# LM3478.net
KiCad netlist of a schematic drawn in Altium Designer
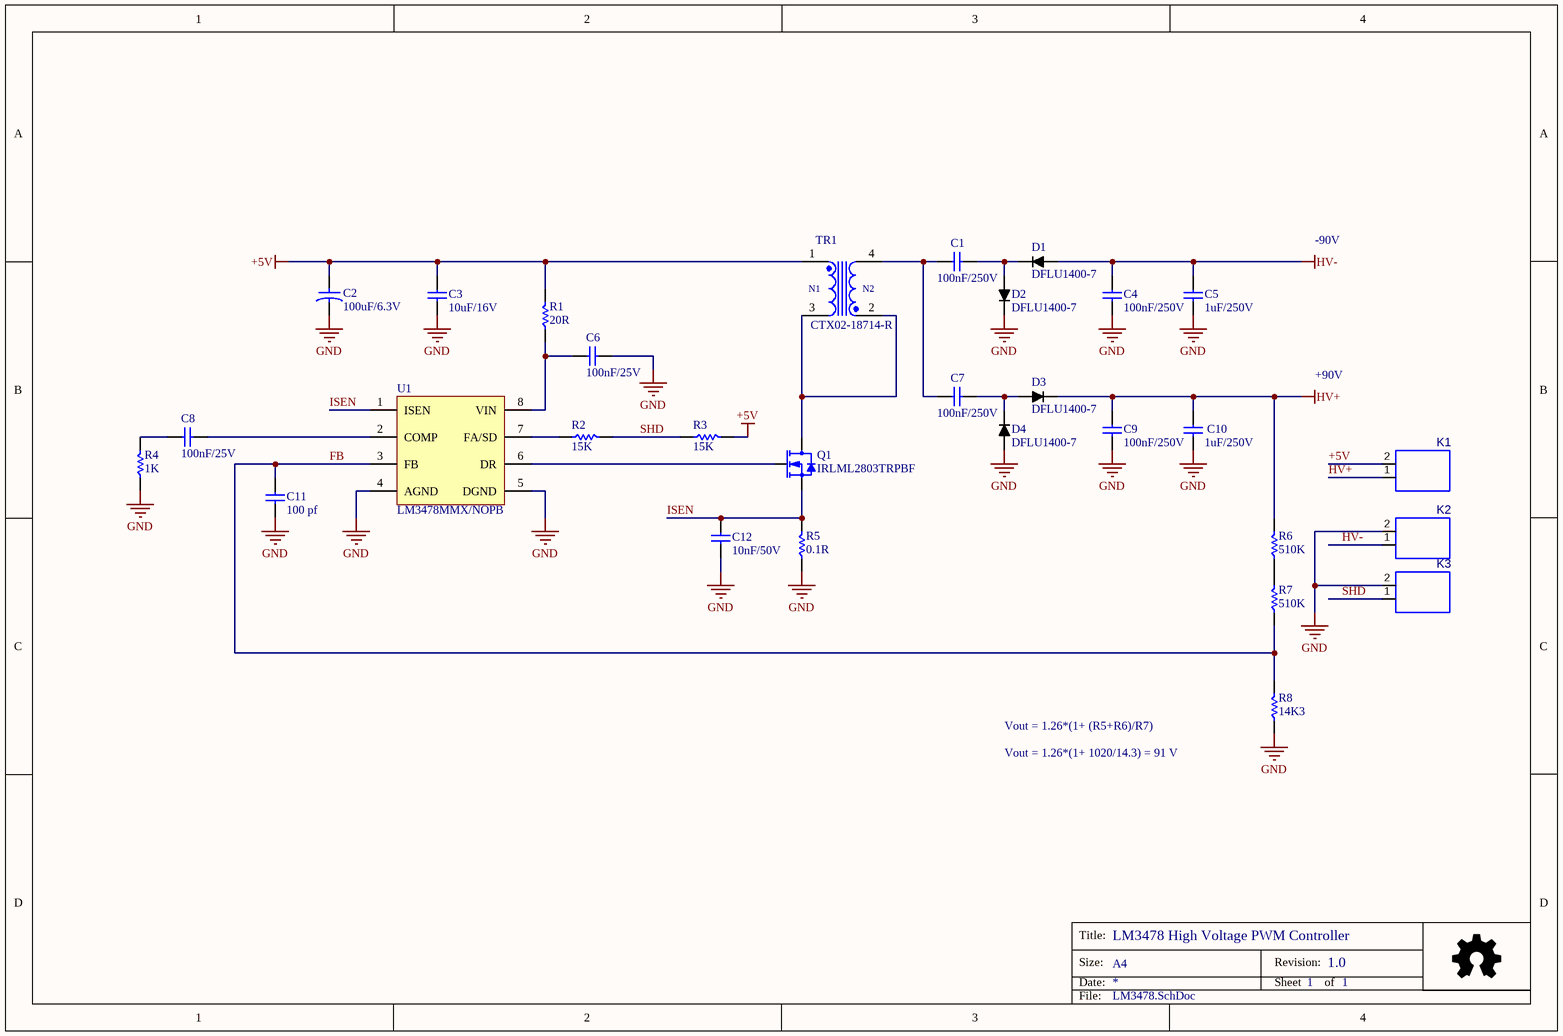
[diagram p0: LM3478.SchDoc]

(export (version "E")
  (design (tool "Eeschema 10.0.6"))
  (components
    (comp (ref "C1")
      (value "100nF/250V")
      (footprint "CAP 0805/2012")
      (description "CAPACITOR 0805 100nF 250V, 10%, X7T")
      (fields
        (field (name "MANUFACTURER") "TDK")
        (field (name "MANUFACTURER PART NUMBER") "CGA4J3X7T2E104K125AA")
      )
      (libsource (lib "LM3478") (part "CGA4J3X7T2E104K125AA"))
    )
    (comp (ref "C2")
      (value "100uF/6.3V")
      (footprint "CAP CASE C")
      (description "CAPACITOR 100uF 2312 6V3 TANT")
      (fields
        (field (name "MANUFACTURER") "Kyocera AVX")
        (field (name "MANUFACTURER PART NUMBER") "TPSC107M006R0150")
      )
      (libsource (lib "LM3478") (part "TPSC107M006R0150"))
    )
    (comp (ref "C3")
      (value "10uF/16V")
      (footprint "CAP 1206/3216")
      (description "CAPACITOR 1206 10uF 16V X7R 10%")
      (fields
        (field (name "MANUFACTURER") "Murata")
        (field (name "MANUFACTURER PART NUMBER") "GCM31CR71C106KA64L")
      )
      (libsource (lib "LM3478") (part "GCM31CR71C106KA64L"))
    )
    (comp (ref "C4")
      (value "100nF/250V")
      (footprint "CAP 0805/2012")
      (description "CAPACITOR 0805 100nF 250V, 10%, X7T")
      (fields
        (field (name "MANUFACTURER") "TDK")
        (field (name "MANUFACTURER PART NUMBER") "CGA4J3X7T2E104K125AA")
      )
      (libsource (lib "LM3478") (part "CGA4J3X7T2E104K125AA"))
    )
    (comp (ref "C5")
      (value "1uF/250V")
      (footprint "CAP 2220/5650")
      (description "CAPACITOR 2220 1uF 250V X7R")
      (fields
        (field (name "MANUFACTURER") "Murata")
        (field (name "MANUFACTURER PART NUMBER") "GRM55DR72E105KW01L")
      )
      (libsource (lib "LM3478") (part "GRM55DR72E105KW01L"))
    )
    (comp (ref "C6")
      (value "100nF/25V")
      (footprint "CAP 0805/2012")
      (description "CAPACITOR 0805 100nF 25V X7R 10%")
      (fields
        (field (name "MANUFACTURER") "Murata")
        (field (name "MANUFACTURER PART NUMBER") "GRM21BR71E104KA01L")
      )
      (libsource (lib "LM3478") (part "GRM21BR71E104KA01L"))
    )
    (comp (ref "C7")
      (value "100nF/250V")
      (footprint "CAP 0805/2012")
      (description "CAPACITOR 0805 100nF 250V, 10%, X7T")
      (fields
        (field (name "MANUFACTURER") "TDK")
        (field (name "MANUFACTURER PART NUMBER") "CGA4J3X7T2E104K125AA")
      )
      (libsource (lib "LM3478") (part "CGA4J3X7T2E104K125AA"))
    )
    (comp (ref "C8")
      (value "100nF/25V")
      (footprint "CAP 0805/2012")
      (description "CAPACITOR 0805 100nF 25V X7R 10%")
      (fields
        (field (name "MANUFACTURER") "Murata")
        (field (name "MANUFACTURER PART NUMBER") "GRM21BR71E104KA01L")
      )
      (libsource (lib "LM3478") (part "GRM21BR71E104KA01L"))
    )
    (comp (ref "C9")
      (value "100nF/250V")
      (footprint "CAP 0805/2012")
      (description "CAPACITOR 0805 100nF 250V, 10%, X7T")
      (fields
        (field (name "MANUFACTURER") "TDK")
        (field (name "MANUFACTURER PART NUMBER") "CGA4J3X7T2E104K125AA")
      )
      (libsource (lib "LM3478") (part "CGA4J3X7T2E104K125AA"))
    )
    (comp (ref "C10")
      (value "1uF/250V")
      (footprint "CAP 2220/5650")
      (description "CAPACITOR 2220 1uF 250V X7R")
      (fields
        (field (name "MANUFACTURER") "Murata")
        (field (name "MANUFACTURER PART NUMBER") "GRM55DR72E105KW01L")
      )
      (libsource (lib "LM3478") (part "GRM55DR72E105KW01L"))
    )
    (comp (ref "C11")
      (value "100 pf")
      (footprint "CAP 0805/2012")
      (description "CAPACITOR 0805 1nF 50V X7R 10%")
      (fields
        (field (name "MANUFACTURER") "Murata")
        (field (name "MANUFACTURER PART NUMBER") "GRM216R71H102KA01D")
      )
      (libsource (lib "LM3478") (part "GRM216R71H102KA01D"))
    )
    (comp (ref "C12")
      (value "10nF/50V")
      (footprint "CAP 0805/2012")
      (description "CAPACITOR 0805 10nF 50V X7R 5%")
      (fields
        (field (name "MANUFACTURER") "Murata")
        (field (name "MANUFACTURER PART NUMBER") "GRM216R71H103JA01D")
      )
      (libsource (lib "LM3478") (part "GRM216R71H103JA01D"))
    )
    (comp (ref "D1")
      (value "DFLU1400-7")
      (footprint "POWERDI-123")
      (description "DIODE 400V 1A POWERDI123")
      (fields (field (name "MANUFACTURER") "Diodes"))
      (libsource (lib "LM3478") (part "DFLU1400-7"))
    )
    (comp (ref "D2")
      (value "DFLU1400-7")
      (footprint "POWERDI-123")
      (description "DIODE 400V 1A POWERDI123")
      (fields (field (name "MANUFACTURER") "Diodes"))
      (libsource (lib "LM3478") (part "DFLU1400-7"))
    )
    (comp (ref "D3")
      (value "DFLU1400-7")
      (footprint "POWERDI-123")
      (description "DIODE 400V 1A POWERDI123")
      (fields (field (name "MANUFACTURER") "Diodes"))
      (libsource (lib "LM3478") (part "DFLU1400-7"))
    )
    (comp (ref "D4")
      (value "DFLU1400-7")
      (footprint "POWERDI-123")
      (description "DIODE 400V 1A POWERDI123")
      (fields (field (name "MANUFACTURER") "Diodes"))
      (libsource (lib "LM3478") (part "DFLU1400-7"))
    )
    (comp (ref "K1") (value "1x2PLS") (footprint "JUMPER2") (libsource (lib "LM3478") (part "1x2PLS")))
    (comp (ref "K2") (value "1x2PLS") (footprint "JUMPER2") (libsource (lib "LM3478") (part "1x2PLS")))
    (comp (ref "K3") (value "1x2PLS") (footprint "JUMPER2") (libsource (lib "LM3478") (part "1x2PLS")))
    (comp (ref "Q1")
      (value "IRLML2803TRPBF")
      (footprint "SOT-23-3")
      (description "MOSFET N-CH 30V 1.2A 3-Pin SOT-23 T/R")
      (fields (field (name "MANUFACTURER") "International Rectifier"))
      (libsource (lib "LM3478") (part "IRLML2803TRPBF"))
    )
    (comp (ref "R1")
      (value "20R")
      (footprint "RES 0805/2012")
      (description "RESISTOR 0805 20R 1%")
      (fields
        (field (name "MANUFACTURER") "Panasonic")
        (field (name "MANUFACTURER PART NUMBER") "ERJ-6ENF20R0V")
      )
      (libsource (lib "LM3478") (part "ERJ6ENF20R0V"))
    )
    (comp (ref "R2")
      (value "15K")
      (footprint "RES 0805/2012")
      (description "RESISTOR 0805 15K 1%")
      (fields
        (field (name "MANUFACTURER") "Panasonic")
        (field (name "MANUFACTURER PART NUMBER") "ERJ-6ENF1502V")
      )
      (libsource (lib "LM3478") (part "ERJ6ENF1502V"))
    )
    (comp (ref "R3")
      (value "15K")
      (footprint "RES 0805/2012")
      (description "RESISTOR 0805 15K 1%")
      (fields
        (field (name "MANUFACTURER") "Panasonic")
        (field (name "MANUFACTURER PART NUMBER") "ERJ-6ENF1502V")
      )
      (libsource (lib "LM3478") (part "ERJ6ENF1502V"))
    )
    (comp (ref "R4")
      (value "1K")
      (footprint "RES 0805/2012")
      (description "RESISTOR 0805 1K 1%")
      (fields
        (field (name "MANUFACTURER") "Panasonic")
        (field (name "MANUFACTURER PART NUMBER") "ERJ-6ENF1001V")
      )
      (libsource (lib "LM3478") (part "ERJ6ENF1001V"))
    )
    (comp (ref "R5")
      (value "0.1R")
      (footprint "RES 0805/2012")
      (description "RESISTOR 0805 0.1R 1%")
      (fields
        (field (name "MANUFACTURER") "Panasonic")
        (field (name "MANUFACTURER PART NUMBER") "ERJ6RSFR10V")
      )
      (libsource (lib "LM3478") (part "ERJ6RSFR10V"))
    )
    (comp (ref "R6")
      (value "510K")
      (footprint "RES 0805/2012")
      (description "RESISTOR 0805 510K 1%")
      (fields
        (field (name "MANUFACTURER") "Panasonic")
        (field (name "MANUFACTURER PART NUMBER") "ERJ6ENF5103V")
      )
      (libsource (lib "LM3478") (part "ERJ6ENF5103V"))
    )
    (comp (ref "R7")
      (value "510K")
      (footprint "RES 0805/2012")
      (description "RESISTOR 0805 510K 1%")
      (fields
        (field (name "MANUFACTURER") "Panasonic")
        (field (name "MANUFACTURER PART NUMBER") "ERJ6ENF5103V")
      )
      (libsource (lib "LM3478") (part "ERJ6ENF5103V"))
    )
    (comp (ref "R8")
      (value "14K3")
      (footprint "RES 0805/2012")
      (description "RESISTOR 0805 6K49 1%")
      (fields
        (field (name "MANUFACTURER") "Panasonic")
        (field (name "MANUFACTURER PART NUMBER") "ERJ-6ENF6491V")
      )
      (libsource (lib "LM3478") (part "ERJ6ENF6491V"))
    )
    (comp (ref "TR1")
      (value "CTX02-18714-R")
      (footprint "CTX02-18714-R")
      (description "COUPLED INDUCTOR 1:4")
      (fields (field (name "MANUFACTURER") "Eaton Cooper"))
      (libsource (lib "LM3478") (part "CTX02-18714-R"))
    )
    (comp (ref "U1")
      (value "LM3478MMX/NOPB")
      (footprint "MSOP-8")
      (description "DC/DC Controller 2.97V to 40V Input")
      (fields (field (name "MANUFACTURER") "TI National Semiconductor"))
      (libsource (lib "LM3478") (part "LM3478MMX/NOPB"))
    )
  )
  (nets
    (net (code "1") (name "+5V") (class "Default")
      (node (ref "C2") (pin "1") (pintype "passive"))
      (node (ref "C3") (pin "2") (pinfunction "2_2") (pintype "passive"))
      (node (ref "K1") (pin "2") (pinfunction "2_2") (pintype "passive"))
      (node (ref "R1") (pin "2") (pintype "passive"))
      (node (ref "R3") (pin "2") (pintype "passive"))
      (node (ref "TR1") (pin "1") (pinfunction "1_1") (pintype "passive"))
    )
    (net (code "2") (name "/FB") (class "Default")
      (node (ref "C11") (pin "2") (pinfunction "2_2") (pintype "passive"))
      (node (ref "R7") (pin "1") (pintype "passive"))
      (node (ref "R8") (pin "2") (pintype "passive"))
      (node (ref "U1") (pin "3") (pinfunction "FB_3") (pintype "passive"))
    )
    (net (code "3") (name "/ISEN") (class "Default")
      (node (ref "C12") (pin "2") (pinfunction "2_2") (pintype "passive"))
      (node (ref "Q1") (pin "2") (pinfunction "S_2") (pintype "passive"))
      (node (ref "R5") (pin "2") (pintype "passive"))
      (node (ref "U1") (pin "1") (pinfunction "ISEN_1") (pintype "passive"))
    )
    (net (code "4") (name "/SHD") (class "Default")
      (node (ref "K3") (pin "1") (pinfunction "1_1") (pintype "passive"))
      (node (ref "R2") (pin "2") (pintype "passive"))
      (node (ref "R3") (pin "1") (pintype "passive"))
    )
    (net (code "5") (name "GND") (class "Default")
      (node (ref "C10") (pin "1") (pinfunction "1_1") (pintype "passive"))
      (node (ref "C11") (pin "1") (pinfunction "1_1") (pintype "passive"))
      (node (ref "C12") (pin "1") (pinfunction "1_1") (pintype "passive"))
      (node (ref "C2") (pin "2") (pintype "passive"))
      (node (ref "C3") (pin "1") (pinfunction "1_1") (pintype "passive"))
      (node (ref "C4") (pin "1") (pinfunction "1_1") (pintype "passive"))
      (node (ref "C5") (pin "1") (pinfunction "1_1") (pintype "passive"))
      (node (ref "C6") (pin "2") (pinfunction "2_2") (pintype "passive"))
      (node (ref "C9") (pin "1") (pinfunction "1_1") (pintype "passive"))
      (node (ref "D2") (pin "1") (pinfunction "K_1") (pintype "passive"))
      (node (ref "D4") (pin "2") (pinfunction "A_2") (pintype "passive"))
      (node (ref "K2") (pin "2") (pinfunction "2_2") (pintype "passive"))
      (node (ref "K3") (pin "2") (pinfunction "2_2") (pintype "passive"))
      (node (ref "R4") (pin "1") (pintype "passive"))
      (node (ref "R5") (pin "1") (pintype "passive"))
      (node (ref "R8") (pin "1") (pintype "passive"))
      (node (ref "U1") (pin "4") (pinfunction "AGND_4") (pintype "passive"))
      (node (ref "U1") (pin "5") (pinfunction "DGND_5") (pintype "passive"))
    )
    (net (code "6") (name "HV+") (class "Default")
      (node (ref "C10") (pin "2") (pinfunction "2_2") (pintype "passive"))
      (node (ref "C9") (pin "2") (pinfunction "2_2") (pintype "passive"))
      (node (ref "D3") (pin "1") (pinfunction "K_1") (pintype "passive"))
      (node (ref "K1") (pin "1") (pinfunction "1_1") (pintype "passive"))
      (node (ref "R6") (pin "2") (pintype "passive"))
    )
    (net (code "7") (name "HV-") (class "Default")
      (node (ref "C4") (pin "2") (pinfunction "2_2") (pintype "passive"))
      (node (ref "C5") (pin "2") (pinfunction "2_2") (pintype "passive"))
      (node (ref "D1") (pin "2") (pinfunction "A_2") (pintype "passive"))
      (node (ref "K2") (pin "1") (pinfunction "1_1") (pintype "passive"))
    )
    (net (code "8") (name "Net-(C1-Pad1)") (class "Default")
      (node (ref "C1") (pin "1") (pinfunction "1_1") (pintype "passive"))
      (node (ref "C7") (pin "1") (pinfunction "1_1") (pintype "passive"))
      (node (ref "TR1") (pin "4") (pinfunction "4_4") (pintype "passive"))
    )
    (net (code "9") (name "Net-(C8-Pad1)") (class "Default")
      (node (ref "C8") (pin "1") (pinfunction "1_1") (pintype "passive"))
      (node (ref "R4") (pin "2") (pintype "passive"))
    )
    (net (code "10") (name "Net-(D1-K)") (class "Default")
      (node (ref "C1") (pin "2") (pinfunction "2_2") (pintype "passive"))
      (node (ref "D1") (pin "1") (pinfunction "K_1") (pintype "passive"))
      (node (ref "D2") (pin "2") (pinfunction "A_2") (pintype "passive"))
    )
    (net (code "11") (name "Net-(D3-A)") (class "Default")
      (node (ref "C7") (pin "2") (pinfunction "2_2") (pintype "passive"))
      (node (ref "D3") (pin "2") (pinfunction "A_2") (pintype "passive"))
      (node (ref "D4") (pin "1") (pinfunction "K_1") (pintype "passive"))
    )
    (net (code "12") (name "Net-(Q1-D)") (class "Default")
      (node (ref "Q1") (pin "3") (pinfunction "D_3") (pintype "passive"))
      (node (ref "TR1") (pin "2") (pinfunction "2_2") (pintype "passive"))
      (node (ref "TR1") (pin "3") (pinfunction "3_3") (pintype "passive"))
    )
    (net (code "13") (name "Net-(Q1-G)") (class "Default")
      (node (ref "Q1") (pin "1") (pinfunction "G_1") (pintype "passive"))
      (node (ref "U1") (pin "6") (pinfunction "DR_6") (pintype "passive"))
    )
    (net (code "14") (name "Net-(R6-Pad1)") (class "Default")
      (node (ref "R6") (pin "1") (pintype "passive"))
      (node (ref "R7") (pin "2") (pintype "passive"))
    )
    (net (code "15") (name "Net-(U1-COMP)") (class "Default")
      (node (ref "C8") (pin "2") (pinfunction "2_2") (pintype "passive"))
      (node (ref "U1") (pin "2") (pinfunction "COMP_2") (pintype "passive"))
    )
    (net (code "16") (name "Net-(U1-FA{slash}SD)") (class "Default")
      (node (ref "R2") (pin "1") (pintype "passive"))
      (node (ref "U1") (pin "7") (pinfunction "FA/SD_7") (pintype "passive"))
    )
    (net (code "17") (name "Net-(U1-VIN)") (class "Default")
      (node (ref "C6") (pin "1") (pinfunction "1_1") (pintype "passive"))
      (node (ref "R1") (pin "1") (pintype "passive"))
      (node (ref "U1") (pin "8") (pinfunction "VIN_8") (pintype "passive"))
    )
  )
)
